# 1__Power_Supply.net
KiCad netlist of a schematic drawn in Altium Designer
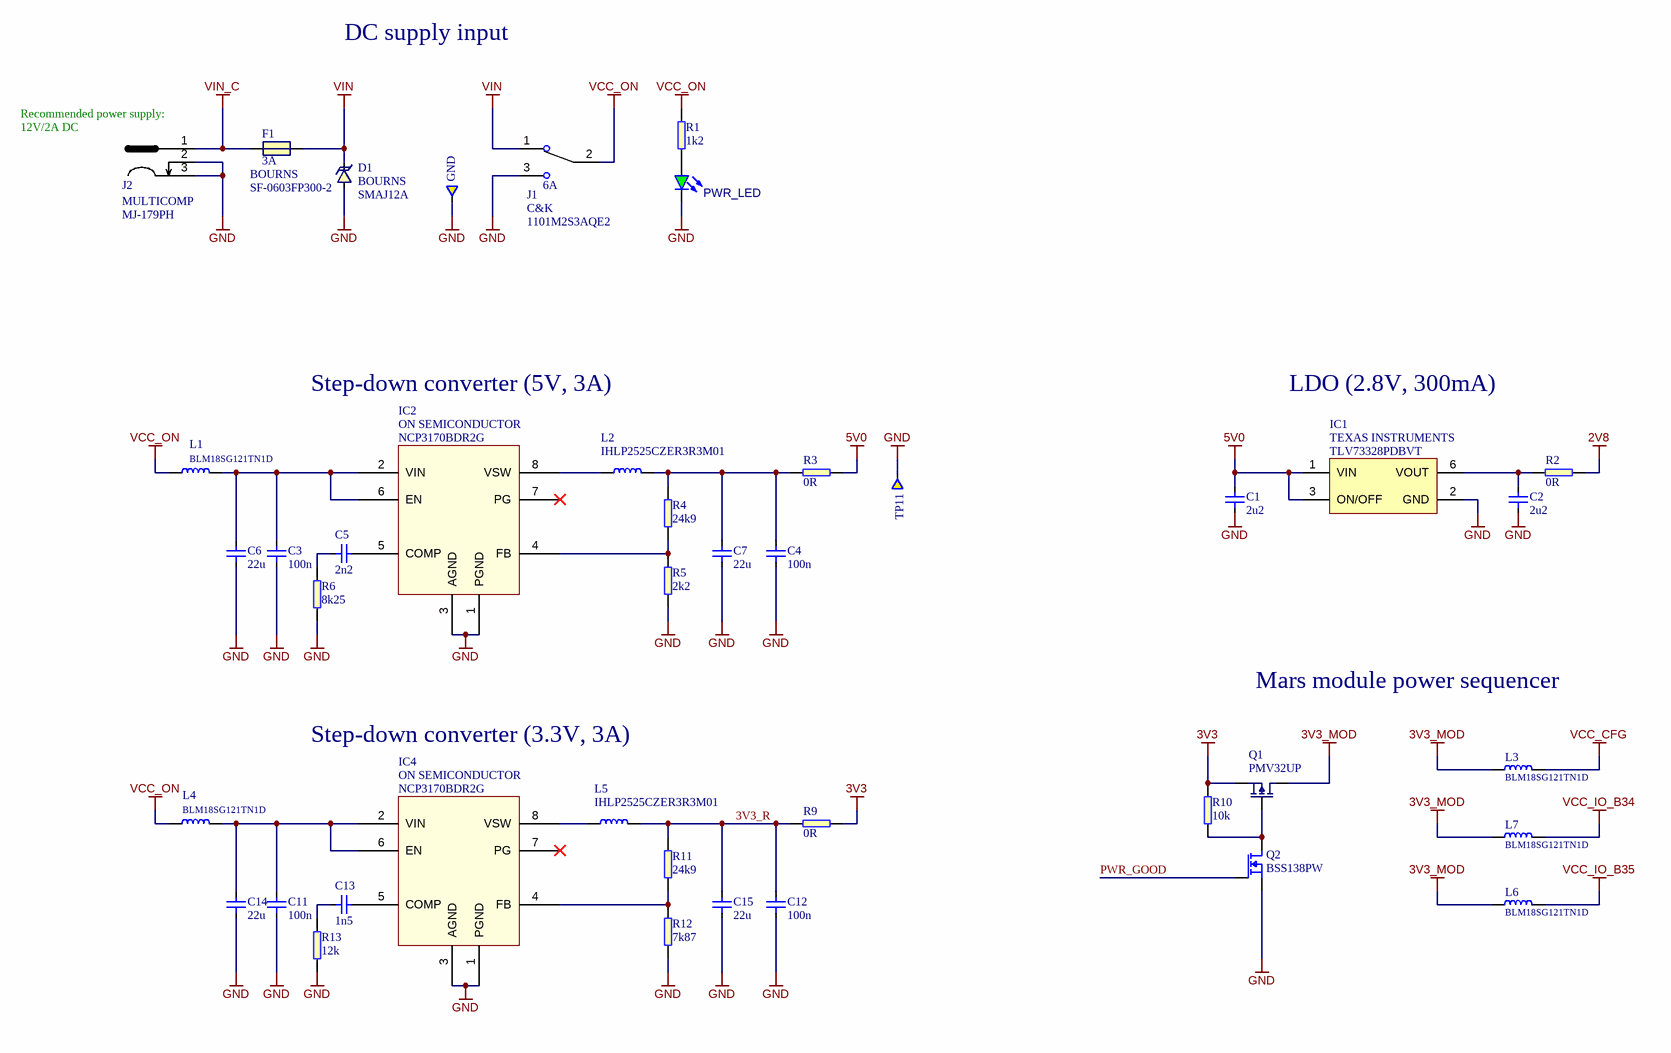
[diagram p0: [1]_Power Supply.SchDoc]

(export (version "E")
  (design (tool "Eeschema 10.0.6"))
  (components
    (comp (ref "C1")
      (value "2u2")
      (footprint "0603")
      (description "MLCC SMT Capacitor 2u2F 0603")
      (fields (field (name "PART NUMBER") "C_2u2_0603") (field (name "VOLTAGE") "35V"))
      (libsource (lib "Zynq-Video-Board-Rev-1.2") (part "C_2u2_0603"))
    )
    (comp (ref "C2")
      (value "2u2")
      (footprint "0603")
      (description "MLCC SMT Capacitor 2u2F 0603")
      (fields (field (name "PART NUMBER") "C_2u2_0603") (field (name "VOLTAGE") "35V"))
      (libsource (lib "Zynq-Video-Board-Rev-1.2") (part "C_2u2_0603"))
    )
    (comp (ref "C3")
      (value "100n")
      (footprint "0402")
      (description "MLCC SMT Capacitor 100nF 0402")
      (fields (field (name "PART NUMBER") "C_100n_0402") (field (name "VOLTAGE") "10V"))
      (libsource (lib "Zynq-Video-Board-Rev-1.2") (part "C_100n_0402"))
    )
    (comp (ref "C4")
      (value "100n")
      (footprint "0402")
      (description "MLCC SMT Capacitor 100nF 0402")
      (fields (field (name "PART NUMBER") "C_100n_0402") (field (name "VOLTAGE") "10V"))
      (libsource (lib "Zynq-Video-Board-Rev-1.2") (part "C_100n_0402"))
    )
    (comp (ref "C5")
      (value "2n2")
      (footprint "0402")
      (description "MLCC SMT Capacitor 2n2 0402")
      (fields (field (name "PART NUMBER") "C_2n2_0402") (field (name "VOLTAGE") "25V"))
      (libsource (lib "Zynq-Video-Board-Rev-1.2") (part "C_2n2_0402"))
    )
    (comp (ref "C6")
      (value "22u")
      (footprint "0805")
      (description "MLCC SMT Capacitor 22uF 0805")
      (fields (field (name "PART NUMBER") "C_22u_0805") (field (name "VOLTAGE") "6.3V"))
      (libsource (lib "Zynq-Video-Board-Rev-1.2") (part "C_22u_0805"))
    )
    (comp (ref "C7")
      (value "22u")
      (footprint "0805")
      (description "MLCC SMT Capacitor 22uF 0805")
      (fields (field (name "PART NUMBER") "C_22u_0805") (field (name "VOLTAGE") "6.3V"))
      (libsource (lib "Zynq-Video-Board-Rev-1.2") (part "C_22u_0805"))
    )
    (comp (ref "C11")
      (value "100n")
      (footprint "0402")
      (description "MLCC SMT Capacitor 100nF 0402")
      (fields (field (name "PART NUMBER") "C_100n_0402") (field (name "VOLTAGE") "10V"))
      (libsource (lib "Zynq-Video-Board-Rev-1.2") (part "C_100n_0402"))
    )
    (comp (ref "C12")
      (value "100n")
      (footprint "0402")
      (description "MLCC SMT Capacitor 100nF 0402")
      (fields (field (name "PART NUMBER") "C_100n_0402") (field (name "VOLTAGE") "10V"))
      (libsource (lib "Zynq-Video-Board-Rev-1.2") (part "C_100n_0402"))
    )
    (comp (ref "C13")
      (value "1n5")
      (footprint "0402")
      (description "MLCC SMT Capacitor 1.5 nF 0402")
      (fields (field (name "PART NUMBER") "C_1n5_0402") (field (name "VOLTAGE") "10V"))
      (libsource (lib "Zynq-Video-Board-Rev-1.2") (part "C_1n5_0402"))
    )
    (comp (ref "C14")
      (value "22u")
      (footprint "0805")
      (description "MLCC SMT Capacitor 22uF 0805")
      (fields (field (name "PART NUMBER") "C_22u_0805") (field (name "VOLTAGE") "6.3V"))
      (libsource (lib "Zynq-Video-Board-Rev-1.2") (part "C_22u_0805"))
    )
    (comp (ref "C15")
      (value "22u")
      (footprint "0805")
      (description "MLCC SMT Capacitor 22uF 0805")
      (fields (field (name "PART NUMBER") "C_22u_0805") (field (name "VOLTAGE") "6.3V"))
      (libsource (lib "Zynq-Video-Board-Rev-1.2") (part "C_22u_0805"))
    )
    (comp (ref "D1")
      (value "SMAJ12A")
      (footprint "DO-214AA")
      (description "DIODE, TVS, 12V, 400W")
      (fields (field (name "MANUFACTURER") "BOURNS"))
      (libsource (lib "Zynq-Video-Board-Rev-1.2") (part "TVS_UNIDIR"))
    )
    (comp (ref "F1")
      (value "3A")
      (footprint "0603")
      (description "Fuse, Surface Mount,  SinglFuse SF-0603FP Series, 3 A, 32 VDC, Fast Acting, 0603")
      (fields
        (field (name "PART NUMBER") "SF-0603FP300-2")
        (field (name "MANUFACTURER") "BOURNS")
        (field (name "PART SYMBOL") "SF-0603FP300-2")
      )
      (libsource (lib "Zynq-Video-Board-Rev-1.2") (part "Fuse"))
    )
    (comp (ref "GND")
      (value "Testpad")
      (footprint "TP-R-2")
      (description "Testpad, round, 2mm")
      (fields (field (name "PART NUMBER") "TP-R-2"))
      (libsource (lib "Zynq-Video-Board-Rev-1.2") (part "Testpad"))
    )
    (comp (ref "IC1")
      (value "TLV73328PDBVT")
      (footprint "SOT23-5N")
      (description "Capacitor-Free, 300-mA, Low-Dropout Regulator with Foldback Current Limit for Portable Devices")
      (fields (field (name "MANUFACTURER") "TEXAS INSTRUMENTS"))
      (libsource (lib "Zynq-Video-Board-Rev-1.2") (part "TLV73328PDBVT"))
    )
    (comp (ref "IC2")
      (value "NCP3170BDR2G")
      (footprint "SOIC-8")
      (description "DC-DC buck (step-down), reg., 4.5V-18Vin, Vou 1.25V-5V/3A, 1 MHz, SOIC-8")
      (fields (field (name "MANUFACTURER") "ON SEMICONDUCTOR"))
      (libsource (lib "Zynq-Video-Board-Rev-1.2") (part "NCP3170BDR2G"))
    )
    (comp (ref "IC4")
      (value "NCP3170BDR2G")
      (footprint "SOIC-8")
      (description "DC-DC buck (step-down), reg., 4.5V-18Vin, Vou 1.25V-5V/3A, 1 MHz, SOIC-8")
      (fields (field (name "MANUFACTURER") "ON SEMICONDUCTOR"))
      (libsource (lib "Zynq-Video-Board-Rev-1.2") (part "NCP3170BDR2G"))
    )
    (comp (ref "J1")
      (value "6A")
      (footprint "1101M2S3AQE2")
      (fields
        (field (name "PART NUMBER") "SPDT Switch")
        (field (name "MANUFACTURER") "C&K")
        (field (name "PART SYMBOL") "1101M2S3AQE2")
      )
      (libsource (lib "Zynq-Video-Board-Rev-1.2") (part "1101M2S3AQE2"))
    )
    (comp (ref "J2")
      (value "~")
      (footprint "DC_SOCKET")
      (fields
        (field (name "PART NUMBER") "DC_SOCKET")
        (field (name "MANUFACTURER") "MULTICOMP")
        (field (name "PART SYMBOL") "MJ-179PH")
      )
      (libsource (lib "Zynq-Video-Board-Rev-1.2") (part "DC_SOCKET"))
    )
    (comp (ref "L1")
      (value "BLM18SG121TN1D")
      (footprint "0603")
      (description "FERRITE BEAD, 0.025OHM, 3A, 0603")
      (fields (field (name "MANUFACTURER") "MURATA"))
      (libsource (lib "Zynq-Video-Board-Rev-1.2") (part "BLM18SG121TN1D"))
    )
    (comp (ref "L2")
      (value "IHLP2525CZER3R3M01")
      (footprint "IHLP-2525CZ-01")
      (description "3.3 µH, ± 20%, Shielded, 0.02 ohm, 8 A")
      (fields (field (name "MANUFACTURER") "VISHAY"))
      (libsource (lib "Zynq-Video-Board-Rev-1.2") (part "Inductor Power"))
    )
    (comp (ref "L3")
      (value "BLM18SG121TN1D")
      (footprint "0603")
      (description "FERRITE BEAD, 0.025OHM, 3A, 0603")
      (fields (field (name "MANUFACTURER") "MURATA"))
      (libsource (lib "Zynq-Video-Board-Rev-1.2") (part "BLM18SG121TN1D"))
    )
    (comp (ref "L4")
      (value "BLM18SG121TN1D")
      (footprint "0603")
      (description "FERRITE BEAD, 0.025OHM, 3A, 0603")
      (fields (field (name "MANUFACTURER") "MURATA"))
      (libsource (lib "Zynq-Video-Board-Rev-1.2") (part "BLM18SG121TN1D"))
    )
    (comp (ref "L5")
      (value "IHLP2525CZER3R3M01")
      (footprint "IHLP-2525CZ-01")
      (description "3.3 µH, ± 20%, Shielded, 0.02 ohm, 8 A")
      (fields (field (name "MANUFACTURER") "VISHAY"))
      (libsource (lib "Zynq-Video-Board-Rev-1.2") (part "Inductor Power"))
    )
    (comp (ref "L6")
      (value "BLM18SG121TN1D")
      (footprint "0603")
      (description "FERRITE BEAD, 0.025OHM, 3A, 0603")
      (fields (field (name "MANUFACTURER") "MURATA"))
      (libsource (lib "Zynq-Video-Board-Rev-1.2") (part "BLM18SG121TN1D"))
    )
    (comp (ref "L7")
      (value "BLM18SG121TN1D")
      (footprint "0603")
      (description "FERRITE BEAD, 0.025OHM, 3A, 0603")
      (fields (field (name "MANUFACTURER") "MURATA"))
      (libsource (lib "Zynq-Video-Board-Rev-1.2") (part "BLM18SG121TN1D"))
    )
    (comp (ref "PWR_LED")
      (value "KPT-1608SGC")
      (footprint "LED0603")
      (description "LED Green 0603 case")
      (fields (field (name "PART NUMBER") "LED_G") (field (name "MANUFACTURER") "KINGBRIGHT"))
      (libsource (lib "Zynq-Video-Board-Rev-1.2") (part "LED"))
    )
    (comp (ref "Q1")
      (value "PMV32UP")
      (footprint "SOT-23")
      (description "P CH, 20V, 4A")
      (fields (field (name "MANUFACTURER") "NXP"))
      (libsource (lib "Zynq-Video-Board-Rev-1.2") (part "PMOS"))
    )
    (comp (ref "Q2")
      (value "BSS138PW")
      (footprint "SC70-3")
      (description "MOSFET, N CH, 60V, 0.2A")
      (fields (field (name "MANUFACTURER") "NXP"))
      (libsource (lib "Zynq-Video-Board-Rev-1.2") (part "NMOS"))
    )
    (comp (ref "R1")
      (value "1k2")
      (footprint "0402")
      (description "SMT Resistor 1k2 0402")
      (fields (field (name "PART NUMBER") "R_1k2_0402") (field (name "TOLERANCE") "1%"))
      (libsource (lib "Zynq-Video-Board-Rev-1.2") (part "R_1k2_0402"))
    )
    (comp (ref "R2")
      (value "0R")
      (footprint "0603")
      (description "SMT Resistor 0R 0603")
      (fields (field (name "PART NUMBER") "R_0R_0603") (field (name "TOLERANCE") "5%"))
      (libsource (lib "Zynq-Video-Board-Rev-1.2") (part "R_0R_0603"))
    )
    (comp (ref "R3")
      (value "0R")
      (footprint "0603")
      (description "SMT Resistor 0R 0603")
      (fields (field (name "PART NUMBER") "R_0R_0603") (field (name "TOLERANCE") "5%"))
      (libsource (lib "Zynq-Video-Board-Rev-1.2") (part "R_0R_0603"))
    )
    (comp (ref "R4")
      (value "24k9")
      (footprint "0402")
      (description "SMT Resistor 24k9 0402")
      (fields (field (name "PART NUMBER") "R_24k9_0402") (field (name "TOLERANCE") "1%"))
      (libsource (lib "Zynq-Video-Board-Rev-1.2") (part "R_24k9_0402"))
    )
    (comp (ref "R5")
      (value "2k2")
      (footprint "0402")
      (description "SMT Resistor 4k7 0402")
      (fields (field (name "PART NUMBER") "R_4k7_0402") (field (name "TOLERANCE") "5%"))
      (libsource (lib "Zynq-Video-Board-Rev-1.2") (part "R_4k7_0402"))
    )
    (comp (ref "R6")
      (value "8k25")
      (footprint "0402")
      (description "SMT Resistor 8k25 0402")
      (fields (field (name "PART NUMBER") "R_8k25_0402") (field (name "TOLERANCE") "1%"))
      (libsource (lib "Zynq-Video-Board-Rev-1.2") (part "R_8k25_0402"))
    )
    (comp (ref "R9")
      (value "0R")
      (footprint "0603")
      (description "SMT Resistor 0R 0603")
      (fields (field (name "PART NUMBER") "R_0R_0603") (field (name "TOLERANCE") "5%"))
      (libsource (lib "Zynq-Video-Board-Rev-1.2") (part "R_0R_0603"))
    )
    (comp (ref "R10")
      (value "10k")
      (footprint "0402")
      (description "SMT Resistor 10k 0402")
      (fields (field (name "PART NUMBER") "R_10k_0402") (field (name "TOLERANCE") "1%"))
      (libsource (lib "Zynq-Video-Board-Rev-1.2") (part "R_10k_0402"))
    )
    (comp (ref "R11")
      (value "24k9")
      (footprint "0402")
      (description "SMT Resistor 24k9 0402")
      (fields (field (name "PART NUMBER") "R_24k9_0402") (field (name "TOLERANCE") "1%"))
      (libsource (lib "Zynq-Video-Board-Rev-1.2") (part "R_24k9_0402"))
    )
    (comp (ref "R12")
      (value "7k87")
      (footprint "0402")
      (description "SMT Resistor 7k87 0402")
      (fields (field (name "PART NUMBER") "R_7k87_0402") (field (name "TOLERANCE") "1%"))
      (libsource (lib "Zynq-Video-Board-Rev-1.2") (part "R_7k87_0402"))
    )
    (comp (ref "R13")
      (value "12k")
      (footprint "0402")
      (description "SMT Resistor 12k 0402")
      (fields (field (name "PART NUMBER") "R_12k_0402") (field (name "TOLERANCE") "1%"))
      (libsource (lib "Zynq-Video-Board-Rev-1.2") (part "R_12k_0402"))
    )
    (comp (ref "TP11")
      (value "Testpad")
      (footprint "TP-R-2")
      (description "Testpad, round, 2mm")
      (fields (field (name "PART NUMBER") "TP-R-2"))
      (libsource (lib "Zynq-Video-Board-Rev-1.2") (part "Testpad"))
    )
  )
  (nets
    (net (code "1") (name "/3V3_R") (class "Default")
      (node (ref "C12") (pin "2") (pinfunction "2_2") (pintype "passive"))
      (node (ref "C15") (pin "2") (pinfunction "2_2") (pintype "passive"))
      (node (ref "L5") (pin "2") (pintype "passive"))
      (node (ref "R11") (pin "2") (pintype "passive"))
      (node (ref "R9") (pin "1") (pintype "passive"))
    )
    (net (code "2") (name "/PWR_GOOD") (class "Default")
      (node (ref "Q2") (pin "1") (pinfunction "G_1") (pintype "passive"))
    )
    (net (code "3") (name "2V8") (class "Default") (node (ref "R2") (pin "2") (pintype "passive")))
    (net (code "4") (name "3V3") (class "Default")
      (node (ref "Q1") (pin "2") (pinfunction "S_2") (pintype "passive"))
      (node (ref "R10") (pin "2") (pintype "passive"))
      (node (ref "R9") (pin "2") (pintype "passive"))
    )
    (net (code "5") (name "3V3_MOD") (class "Default")
      (node (ref "L3") (pin "1") (pintype "passive"))
      (node (ref "L6") (pin "1") (pintype "passive"))
      (node (ref "L7") (pin "1") (pintype "passive"))
      (node (ref "Q1") (pin "3") (pinfunction "D_3") (pintype "passive"))
    )
    (net (code "6") (name "5V0") (class "Default")
      (node (ref "C1") (pin "2") (pinfunction "2_2") (pintype "passive"))
      (node (ref "IC1") (pin "1") (pinfunction "VIN_1") (pintype "passive"))
      (node (ref "IC1") (pin "3") (pinfunction "ON/OFF_3") (pintype "passive"))
      (node (ref "R3") (pin "2") (pintype "passive"))
    )
    (net (code "7") (name "GND") (class "Default")
      (node (ref "C1") (pin "1") (pinfunction "1_1") (pintype "passive"))
      (node (ref "C11") (pin "1") (pinfunction "1_1") (pintype "passive"))
      (node (ref "C12") (pin "1") (pinfunction "1_1") (pintype "passive"))
      (node (ref "C14") (pin "1") (pinfunction "1_1") (pintype "passive"))
      (node (ref "C15") (pin "1") (pinfunction "1_1") (pintype "passive"))
      (node (ref "C2") (pin "1") (pinfunction "1_1") (pintype "passive"))
      (node (ref "C3") (pin "1") (pinfunction "1_1") (pintype "passive"))
      (node (ref "C4") (pin "1") (pinfunction "1_1") (pintype "passive"))
      (node (ref "C6") (pin "1") (pinfunction "1_1") (pintype "passive"))
      (node (ref "C7") (pin "1") (pinfunction "1_1") (pintype "passive"))
      (node (ref "D1") (pin "A") (pinfunction "A_A") (pintype "passive"))
      (node (ref "GND") (pin "1") (pintype "passive"))
      (node (ref "IC1") (pin "2") (pinfunction "GND_2") (pintype "passive"))
      (node (ref "IC2") (pin "1") (pinfunction "PGND_1") (pintype "passive"))
      (node (ref "IC2") (pin "3") (pinfunction "AGND_3") (pintype "passive"))
      (node (ref "IC4") (pin "1") (pinfunction "PGND_1") (pintype "passive"))
      (node (ref "IC4") (pin "3") (pinfunction "AGND_3") (pintype "passive"))
      (node (ref "J1") (pin "3") (pinfunction "3_3") (pintype "passive"))
      (node (ref "J2") (pin "2") (pinfunction "2_2") (pintype "passive"))
      (node (ref "J2") (pin "3") (pinfunction "3_3") (pintype "passive"))
      (node (ref "PWR_LED") (pin "K") (pinfunction "K_K") (pintype "passive"))
      (node (ref "Q2") (pin "2") (pinfunction "S_2") (pintype "passive"))
      (node (ref "R12") (pin "1") (pintype "passive"))
      (node (ref "R13") (pin "1") (pintype "passive"))
      (node (ref "R5") (pin "1") (pintype "passive"))
      (node (ref "R6") (pin "1") (pintype "passive"))
      (node (ref "TP11") (pin "1") (pintype "passive"))
    )
    (net (code "8") (name "Net-(C4-Pad2)") (class "Default")
      (node (ref "C4") (pin "2") (pinfunction "2_2") (pintype "passive"))
      (node (ref "C7") (pin "2") (pinfunction "2_2") (pintype "passive"))
      (node (ref "L2") (pin "2") (pintype "passive"))
      (node (ref "R3") (pin "1") (pintype "passive"))
      (node (ref "R4") (pin "2") (pintype "passive"))
    )
    (net (code "9") (name "Net-(C5-Pad1)") (class "Default")
      (node (ref "C5") (pin "1") (pinfunction "1_1") (pintype "passive"))
      (node (ref "R6") (pin "2") (pintype "passive"))
    )
    (net (code "10") (name "Net-(C13-Pad1)") (class "Default")
      (node (ref "C13") (pin "1") (pinfunction "1_1") (pintype "passive"))
      (node (ref "R13") (pin "2") (pintype "passive"))
    )
    (net (code "11") (name "Net-(IC1-VOUT)") (class "Default")
      (node (ref "C2") (pin "2") (pinfunction "2_2") (pintype "passive"))
      (node (ref "IC1") (pin "6") (pinfunction "VOUT_6") (pintype "passive"))
      (node (ref "R2") (pin "1") (pintype "passive"))
    )
    (net (code "12") (name "Net-(IC2-COMP)") (class "Default")
      (node (ref "C5") (pin "2") (pinfunction "2_2") (pintype "passive"))
      (node (ref "IC2") (pin "5") (pinfunction "COMP_5") (pintype "passive"))
    )
    (net (code "13") (name "Net-(IC2-EN)") (class "Default")
      (node (ref "C3") (pin "2") (pinfunction "2_2") (pintype "passive"))
      (node (ref "C6") (pin "2") (pinfunction "2_2") (pintype "passive"))
      (node (ref "IC2") (pin "2") (pinfunction "VIN_2") (pintype "passive"))
      (node (ref "IC2") (pin "6") (pinfunction "EN_6") (pintype "passive"))
      (node (ref "L1") (pin "2") (pintype "passive"))
    )
    (net (code "14") (name "Net-(IC2-FB)") (class "Default")
      (node (ref "IC2") (pin "4") (pinfunction "FB_4") (pintype "passive"))
      (node (ref "R4") (pin "1") (pintype "passive"))
      (node (ref "R5") (pin "2") (pintype "passive"))
    )
    (net (code "15") (name "Net-(IC2-VSW)") (class "Default")
      (node (ref "IC2") (pin "8") (pinfunction "VSW_8") (pintype "passive"))
      (node (ref "L2") (pin "1") (pintype "passive"))
    )
    (net (code "16") (name "Net-(IC4-COMP)") (class "Default")
      (node (ref "C13") (pin "2") (pinfunction "2_2") (pintype "passive"))
      (node (ref "IC4") (pin "5") (pinfunction "COMP_5") (pintype "passive"))
    )
    (net (code "17") (name "Net-(IC4-EN)") (class "Default")
      (node (ref "C11") (pin "2") (pinfunction "2_2") (pintype "passive"))
      (node (ref "C14") (pin "2") (pinfunction "2_2") (pintype "passive"))
      (node (ref "IC4") (pin "2") (pinfunction "VIN_2") (pintype "passive"))
      (node (ref "IC4") (pin "6") (pinfunction "EN_6") (pintype "passive"))
      (node (ref "L4") (pin "2") (pintype "passive"))
    )
    (net (code "18") (name "Net-(IC4-FB)") (class "Default")
      (node (ref "IC4") (pin "4") (pinfunction "FB_4") (pintype "passive"))
      (node (ref "R11") (pin "1") (pintype "passive"))
      (node (ref "R12") (pin "2") (pintype "passive"))
    )
    (net (code "19") (name "Net-(IC4-VSW)") (class "Default")
      (node (ref "IC4") (pin "8") (pinfunction "VSW_8") (pintype "passive"))
      (node (ref "L5") (pin "1") (pintype "passive"))
    )
    (net (code "20") (name "Net-(PWR_LED-PadA)") (class "Default")
      (node (ref "PWR_LED") (pin "A") (pinfunction "A_A") (pintype "passive"))
      (node (ref "R1") (pin "1") (pintype "passive"))
    )
    (net (code "21") (name "Net-(Q1-G)") (class "Default")
      (node (ref "Q1") (pin "1") (pinfunction "G_1") (pintype "passive"))
      (node (ref "Q2") (pin "3") (pinfunction "D_3") (pintype "passive"))
      (node (ref "R10") (pin "1") (pintype "passive"))
    )
    (net (code "22") (name "VCC_CFG") (class "Default") (node (ref "L3") (pin "2") (pintype "passive")))
    (net (code "23") (name "VCC_IO_B34") (class "Default") (node (ref "L7") (pin "2") (pintype "passive")))
    (net (code "24") (name "VCC_IO_B35") (class "Default") (node (ref "L6") (pin "2") (pintype "passive")))
    (net (code "25") (name "VCC_ON") (class "Default")
      (node (ref "J1") (pin "2") (pinfunction "2_2") (pintype "passive"))
      (node (ref "L1") (pin "1") (pintype "passive"))
      (node (ref "L4") (pin "1") (pintype "passive"))
      (node (ref "R1") (pin "2") (pintype "passive"))
    )
    (net (code "26") (name "VIN") (class "Default")
      (node (ref "D1") (pin "C") (pinfunction "C_C") (pintype "passive"))
      (node (ref "F1") (pin "2") (pinfunction "2_2") (pintype "passive"))
      (node (ref "J1") (pin "1") (pinfunction "1_1") (pintype "passive"))
    )
    (net (code "27") (name "VIN_C") (class "Default")
      (node (ref "F1") (pin "1") (pinfunction "1_1") (pintype "passive"))
      (node (ref "J2") (pin "1") (pinfunction "1_1") (pintype "passive"))
    )
    (net (code "28") (name "unconnected-(IC2-PG-Pad7)") (class "Default")
      (node (ref "IC2") (pin "7") (pinfunction "PG_7") (pintype "passive+no_connect"))
    )
    (net (code "29") (name "unconnected-(IC4-PG-Pad7)") (class "Default")
      (node (ref "IC4") (pin "7") (pinfunction "PG_7") (pintype "passive+no_connect"))
    )
  )
)
